# Qwiic_Sound_Trigger.net
KiCad netlist of a schematic drawn in EAGLE
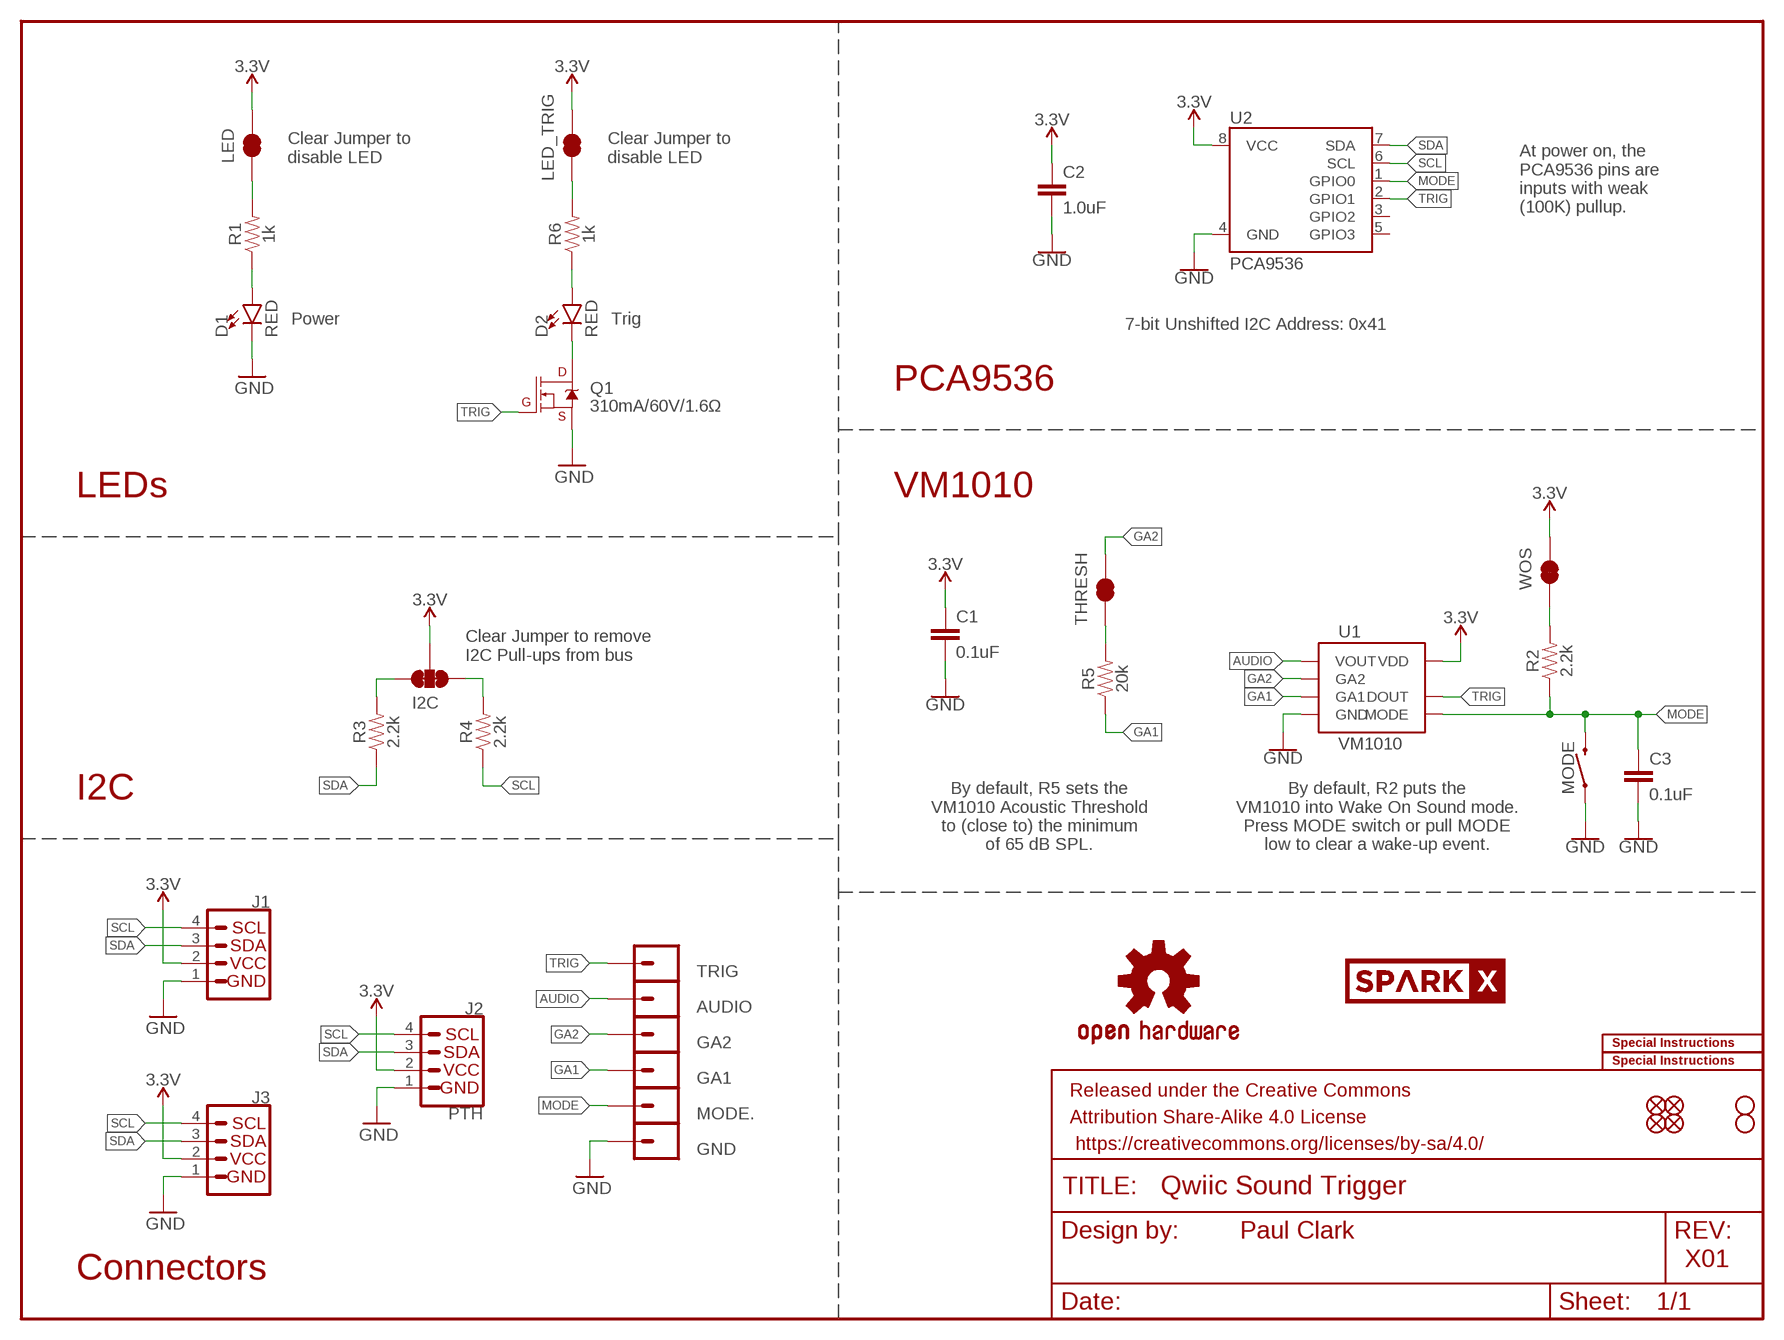
[diagram p0: schematic, sheet 1]

(export (version "E")
  (design (tool "Eeschema 10.0.6"))
  (components
    (comp (ref "AUDIO")
      (value "CONN_01PTH_NO_SILK_YES_STOP")
      (footprint "eagle-import:1X01_NO_SILK")
      (libsource (lib "eagle-import") (part "CONN_01PTH_NO_SILK_YES_STOP"))
    )
    (comp (ref "C1")
      (value "0.1uF")
      (footprint "eagle-import:0603")
      (libsource (lib "eagle-import") (part "0.1UF-0603-25V-(+80/-20%)"))
    )
    (comp (ref "C2")
      (value "1.0uF")
      (footprint "eagle-import:0603")
      (libsource (lib "eagle-import") (part "1.0UF-0603-16V-10%-X7R"))
    )
    (comp (ref "C3")
      (value "0.1uF")
      (footprint "eagle-import:0603")
      (libsource (lib "eagle-import") (part "0.1UF-0603-25V-(+80/-20%)"))
    )
    (comp (ref "D1")
      (value "RED")
      (footprint "eagle-import:LED-0603")
      (libsource (lib "eagle-import") (part "LED-RED0603"))
    )
    (comp (ref "D2")
      (value "RED")
      (footprint "eagle-import:LED-0603")
      (libsource (lib "eagle-import") (part "LED-RED0603"))
    )
    (comp (ref "FRAME1")
      (value "FRAME-LETTER")
      (footprint "eagle-import:CREATIVE_COMMONS")
      (libsource (lib "eagle-import") (part "FRAME-LETTER"))
    )
    (comp (ref "GA1")
      (value "CONN_01PTH_NO_SILK_YES_STOP")
      (footprint "eagle-import:1X01_NO_SILK")
      (libsource (lib "eagle-import") (part "CONN_01PTH_NO_SILK_YES_STOP"))
    )
    (comp (ref "GA2")
      (value "CONN_01PTH_NO_SILK_YES_STOP")
      (footprint "eagle-import:1X01_NO_SILK")
      (libsource (lib "eagle-import") (part "CONN_01PTH_NO_SILK_YES_STOP"))
    )
    (comp (ref "GND")
      (value "CONN_01PTH_NO_SILK_YES_STOP")
      (footprint "eagle-import:1X01_NO_SILK")
      (libsource (lib "eagle-import") (part "CONN_01PTH_NO_SILK_YES_STOP"))
    )
    (comp (ref "I2C")
      (value "JUMPER-SMT_3_2-NC_TRACE_SILK")
      (footprint "eagle-import:SMT-JUMPER_3_2-NC_TRACE_SILK")
      (libsource (lib "eagle-import") (part "JUMPER-SMT_3_2-NC_TRACE_SILK"))
    )
    (comp (ref "J1")
      (value "Qwiic Right Angle")
      (footprint "eagle-import:JST04_1MM_RA")
      (libsource (lib "eagle-import") (part "I2C_STANDARDQWIIC"))
    )
    (comp (ref "J2")
      (value "PTH")
      (footprint "eagle-import:1X04_NO_SILK")
      (libsource (lib "eagle-import") (part "I2C_STANDARD_NO_SILK"))
    )
    (comp (ref "J3")
      (value "Qwiic Right Angle")
      (footprint "eagle-import:JST04_1MM_RA")
      (libsource (lib "eagle-import") (part "I2C_STANDARDQWIIC"))
    )
    (comp (ref "JP1")
      (value "FIDUCIAL1X2")
      (footprint "eagle-import:FIDUCIAL-1X2")
      (libsource (lib "eagle-import") (part "FIDUCIAL1X2"))
    )
    (comp (ref "JP2")
      (value "FIDUCIAL1X2")
      (footprint "eagle-import:FIDUCIAL-1X2")
      (libsource (lib "eagle-import") (part "FIDUCIAL1X2"))
    )
    (comp (ref "JP3")
      (value "STAND-OFF")
      (footprint "eagle-import:STAND-OFF")
      (libsource (lib "eagle-import") (part "STAND-OFF"))
    )
    (comp (ref "JP4")
      (value "STAND-OFF")
      (footprint "eagle-import:STAND-OFF")
      (libsource (lib "eagle-import") (part "STAND-OFF"))
    )
    (comp (ref "JP5")
      (value "FIDUCIAL1X2")
      (footprint "eagle-import:FIDUCIAL-1X2")
      (libsource (lib "eagle-import") (part "FIDUCIAL1X2"))
    )
    (comp (ref "JP6")
      (value "FIDUCIAL1X2")
      (footprint "eagle-import:FIDUCIAL-1X2")
      (libsource (lib "eagle-import") (part "FIDUCIAL1X2"))
    )
    (comp (ref "LED")
      (value "JUMPER-SMT_2_NC_TRACE_SILK")
      (footprint "eagle-import:SMT-JUMPER_2_NC_TRACE_SILK")
      (libsource (lib "eagle-import") (part "JUMPER-SMT_2_NC_TRACE_SILK"))
    )
    (comp (ref "LED_TRIG")
      (value "JUMPER-SMT_2_NC_TRACE_SILK")
      (footprint "eagle-import:SMT-JUMPER_2_NC_TRACE_SILK")
      (libsource (lib "eagle-import") (part "JUMPER-SMT_2_NC_TRACE_SILK"))
    )
    (comp (ref "LOGO1")
      (value "OSHW-LOGOMINI")
      (footprint "eagle-import:OSHW-LOGO-MINI")
      (libsource (lib "eagle-import") (part "OSHW-LOGOMINI"))
    )
    (comp (ref "LOGO2")
      (value "SPECIAL_INSTRUCTIONS-ORDERING")
      (footprint "eagle-import:ORDERING_INSTRUCTIONS")
      (libsource (lib "eagle-import") (part "SPECIAL_INSTRUCTIONS-ORDERING"))
    )
    (comp (ref "LOGO3")
      (value "SPECIAL_INSTRUCTIONS-PRODUCTION")
      (footprint "eagle-import:PRODUCTION_INSTRUCTIONS")
      (libsource (lib "eagle-import") (part "SPECIAL_INSTRUCTIONS-PRODUCTION"))
    )
    (comp (ref "MODE")
      (value "MOMENTARY-SWITCH-SPST-SMD-4.6X2.8MM")
      (footprint "eagle-import:TACTILE_SWITCH_SMD_4.6X2.8MM")
      (libsource (lib "eagle-import") (part "MOMENTARY-SWITCH-SPST-SMD-4.6X2.8MM"))
    )
    (comp (ref "MODE.")
      (value "CONN_01PTH_NO_SILK_YES_STOP")
      (footprint "eagle-import:1X01_NO_SILK")
      (libsource (lib "eagle-import") (part "CONN_01PTH_NO_SILK_YES_STOP"))
    )
    (comp (ref "Q1")
      (value "310mA/60V/1.6Ω")
      (footprint "eagle-import:SOT323")
      (libsource (lib "eagle-import") (part "MOSFET-NCH-2N7002PW"))
    )
    (comp (ref "R1")
      (value "1k")
      (footprint "eagle-import:0603")
      (libsource (lib "eagle-import") (part "1KOHM-0603-1/10W-1%"))
    )
    (comp (ref "R2")
      (value "2.2k")
      (footprint "eagle-import:0603")
      (libsource (lib "eagle-import") (part "2.2KOHM-0603-1/10W-1%"))
    )
    (comp (ref "R3")
      (value "2.2k")
      (footprint "eagle-import:0603")
      (libsource (lib "eagle-import") (part "2.2KOHM-0603-1/10W-1%"))
    )
    (comp (ref "R4")
      (value "2.2k")
      (footprint "eagle-import:0603")
      (libsource (lib "eagle-import") (part "2.2KOHM-0603-1/10W-1%"))
    )
    (comp (ref "R5")
      (value "20k")
      (footprint "eagle-import:0603")
      (libsource (lib "eagle-import") (part "20KOHM-0603-1/10W-1%"))
    )
    (comp (ref "R6")
      (value "1k")
      (footprint "eagle-import:0603")
      (libsource (lib "eagle-import") (part "1KOHM-0603-1/10W-1%"))
    )
    (comp (ref "THRESH")
      (value "JUMPER-SMT_2_NC_TRACE_SILK")
      (footprint "eagle-import:SMT-JUMPER_2_NC_TRACE_SILK")
      (libsource (lib "eagle-import") (part "JUMPER-SMT_2_NC_TRACE_SILK"))
    )
    (comp (ref "TRIG")
      (value "CONN_01PTH_NO_SILK_YES_STOP")
      (footprint "eagle-import:1X01_NO_SILK")
      (libsource (lib "eagle-import") (part "CONN_01PTH_NO_SILK_YES_STOP"))
    )
    (comp (ref "U$2")
      (value "SPARKX-LOGO4")
      (footprint "eagle-import:SPARKX-MEDIUM")
      (libsource (lib "eagle-import") (part "SPARKX-LOGO4"))
    )
    (comp (ref "U1")
      (value "VM1010")
      (footprint "eagle-import:VM1010")
      (fields (field (name "DIGIKEY_PART") "2022-1001-1-ND") (field (name "MANU_PART") "VM1010AA"))
      (libsource (lib "eagle-import") (part "VM1010"))
    )
    (comp (ref "U2")
      (value "PCA9536")
      (footprint "eagle-import:MSOP8")
      (libsource (lib "eagle-import") (part "PCA9536"))
    )
    (comp (ref "WOS")
      (value "JUMPER-SMT_2_NC_TRACE_SILK")
      (footprint "eagle-import:SMT-JUMPER_2_NC_TRACE_SILK")
      (libsource (lib "eagle-import") (part "JUMPER-SMT_2_NC_TRACE_SILK"))
    )
  )
  (nets
    (net (code "1") (name "3.3V") (class "Default")
      (node (ref "C1") (pin "1") (pinfunction "1_1") (pintype "passive"))
      (node (ref "C2") (pin "1") (pinfunction "1_1") (pintype "passive"))
      (node (ref "I2C") (pin "2") (pinfunction "2_2") (pintype "passive"))
      (node (ref "J1") (pin "2") (pinfunction "2_2") (pintype "power_in"))
      (node (ref "J2") (pin "2") (pinfunction "2_2") (pintype "power_in"))
      (node (ref "J3") (pin "2") (pinfunction "2_2") (pintype "power_in"))
      (node (ref "LED") (pin "2") (pinfunction "2_2") (pintype "passive"))
      (node (ref "LED_TRIG") (pin "2") (pinfunction "2_2") (pintype "passive"))
      (node (ref "U1") (pin "6") (pinfunction "VDD_6") (pintype "power_in"))
      (node (ref "U2") (pin "8") (pinfunction "VCC_8") (pintype "bidirectional"))
      (node (ref "WOS") (pin "2") (pinfunction "2_2") (pintype "passive"))
    )
    (net (code "2") (name "AUDIO") (class "Default")
      (node (ref "AUDIO") (pin "1") (pinfunction "1_1") (pintype "passive"))
      (node (ref "U1") (pin "1") (pinfunction "VOUT_1") (pintype "output"))
    )
    (net (code "3") (name "GA1") (class "Default")
      (node (ref "GA1") (pin "1") (pinfunction "1_1") (pintype "passive"))
      (node (ref "R5") (pin "1") (pinfunction "1_1") (pintype "passive"))
      (node (ref "U1") (pin "3") (pinfunction "GA1_3") (pintype "input"))
    )
    (net (code "4") (name "GA2") (class "Default")
      (node (ref "GA2") (pin "1") (pinfunction "1_1") (pintype "passive"))
      (node (ref "THRESH") (pin "2") (pinfunction "2_2") (pintype "passive"))
      (node (ref "U1") (pin "2") (pinfunction "GA2_2") (pintype "input"))
    )
    (net (code "5") (name "GND") (class "Default")
      (node (ref "C1") (pin "2") (pinfunction "2_2") (pintype "passive"))
      (node (ref "C2") (pin "2") (pinfunction "2_2") (pintype "passive"))
      (node (ref "C3") (pin "2") (pinfunction "2_2") (pintype "passive"))
      (node (ref "D1") (pin "C") (pinfunction "C_C") (pintype "passive"))
      (node (ref "GND") (pin "1") (pinfunction "1_1") (pintype "passive"))
      (node (ref "J1") (pin "1") (pinfunction "1_1") (pintype "power_in"))
      (node (ref "J2") (pin "1") (pinfunction "1_1") (pintype "power_in"))
      (node (ref "J3") (pin "1") (pinfunction "1_1") (pintype "power_in"))
      (node (ref "MODE") (pin "1") (pinfunction "1_1") (pintype "passive"))
      (node (ref "MODE") (pin "2") (pinfunction "1_2") (pintype "passive"))
      (node (ref "Q1") (pin "2") (pinfunction "S_2") (pintype "bidirectional"))
      (node (ref "U1") (pin "4") (pinfunction "GND_4") (pintype "power_in"))
      (node (ref "U1") (pin "8") (pinfunction "GND_8") (pintype "power_in"))
      (node (ref "U2") (pin "4") (pinfunction "GND_4") (pintype "bidirectional"))
    )
    (net (code "6") (name "MODE") (class "Default")
      (node (ref "C3") (pin "1") (pinfunction "1_1") (pintype "passive"))
      (node (ref "MODE") (pin "3") (pinfunction "2_3") (pintype "passive"))
      (node (ref "MODE") (pin "4") (pinfunction "2_4") (pintype "passive"))
      (node (ref "MODE.") (pin "1") (pinfunction "1_1") (pintype "passive"))
      (node (ref "R2") (pin "1") (pinfunction "1_1") (pintype "passive"))
      (node (ref "U1") (pin "5") (pinfunction "MODE_5") (pintype "input"))
      (node (ref "U2") (pin "1") (pinfunction "GPIO0_1") (pintype "bidirectional"))
    )
    (net (code "7") (name "Net-(D1-PadA)") (class "Default")
      (node (ref "D1") (pin "A") (pinfunction "A_A") (pintype "passive"))
      (node (ref "R1") (pin "1") (pinfunction "1_1") (pintype "passive"))
    )
    (net (code "8") (name "Net-(D2-PadA)") (class "Default")
      (node (ref "D2") (pin "A") (pinfunction "A_A") (pintype "passive"))
      (node (ref "R6") (pin "1") (pinfunction "1_1") (pintype "passive"))
    )
    (net (code "9") (name "Net-(I2C-Pad1)") (class "Default")
      (node (ref "I2C") (pin "1") (pinfunction "1_1") (pintype "passive"))
      (node (ref "R4") (pin "2") (pinfunction "2_2") (pintype "passive"))
    )
    (net (code "10") (name "Net-(I2C-Pad3)") (class "Default")
      (node (ref "I2C") (pin "3") (pinfunction "3_3") (pintype "passive"))
      (node (ref "R3") (pin "2") (pinfunction "2_2") (pintype "passive"))
    )
    (net (code "11") (name "Net-(LED-Pad1)") (class "Default")
      (node (ref "LED") (pin "1") (pinfunction "1_1") (pintype "passive"))
      (node (ref "R1") (pin "2") (pinfunction "2_2") (pintype "passive"))
    )
    (net (code "12") (name "Net-(LED_TRIG-Pad1)") (class "Default")
      (node (ref "LED_TRIG") (pin "1") (pinfunction "1_1") (pintype "passive"))
      (node (ref "R6") (pin "2") (pinfunction "2_2") (pintype "passive"))
    )
    (net (code "13") (name "Net-(Q1-D)") (class "Default")
      (node (ref "D2") (pin "C") (pinfunction "C_C") (pintype "passive"))
      (node (ref "Q1") (pin "3") (pinfunction "D_3") (pintype "bidirectional"))
    )
    (net (code "14") (name "Net-(R2-Pad2)") (class "Default")
      (node (ref "R2") (pin "2") (pinfunction "2_2") (pintype "passive"))
      (node (ref "WOS") (pin "1") (pinfunction "1_1") (pintype "passive"))
    )
    (net (code "15") (name "Net-(R5-Pad2)") (class "Default")
      (node (ref "R5") (pin "2") (pinfunction "2_2") (pintype "passive"))
      (node (ref "THRESH") (pin "1") (pinfunction "1_1") (pintype "passive"))
    )
    (net (code "16") (name "SCL") (class "Default")
      (node (ref "J1") (pin "4") (pinfunction "4_4") (pintype "passive"))
      (node (ref "J2") (pin "4") (pinfunction "4_4") (pintype "passive"))
      (node (ref "J3") (pin "4") (pinfunction "4_4") (pintype "passive"))
      (node (ref "R4") (pin "1") (pinfunction "1_1") (pintype "passive"))
      (node (ref "U2") (pin "6") (pinfunction "SCL_6") (pintype "bidirectional"))
    )
    (net (code "17") (name "SDA") (class "Default")
      (node (ref "J1") (pin "3") (pinfunction "3_3") (pintype "passive"))
      (node (ref "J2") (pin "3") (pinfunction "3_3") (pintype "passive"))
      (node (ref "J3") (pin "3") (pinfunction "3_3") (pintype "passive"))
      (node (ref "R3") (pin "1") (pinfunction "1_1") (pintype "passive"))
      (node (ref "U2") (pin "7") (pinfunction "SDA_7") (pintype "bidirectional"))
    )
    (net (code "18") (name "TRIG") (class "Default")
      (node (ref "Q1") (pin "1") (pinfunction "G_1") (pintype "bidirectional"))
      (node (ref "TRIG") (pin "1") (pinfunction "1_1") (pintype "passive"))
      (node (ref "U1") (pin "7") (pinfunction "DOUT_7") (pintype "output"))
      (node (ref "U2") (pin "2") (pinfunction "GPIO1_2") (pintype "bidirectional"))
    )
    (net (code "19") (name "unconnected-(U2-GPIO2-Pad3)") (class "Default")
      (node (ref "U2") (pin "3") (pinfunction "GPIO2_3") (pintype "bidirectional"))
    )
    (net (code "20") (name "unconnected-(U2-GPIO3-Pad5)") (class "Default")
      (node (ref "U2") (pin "5") (pinfunction "GPIO3_5") (pintype "bidirectional"))
    )
  )
)
